# KEY.net
KiCad netlist of a schematic drawn in Altium Designer
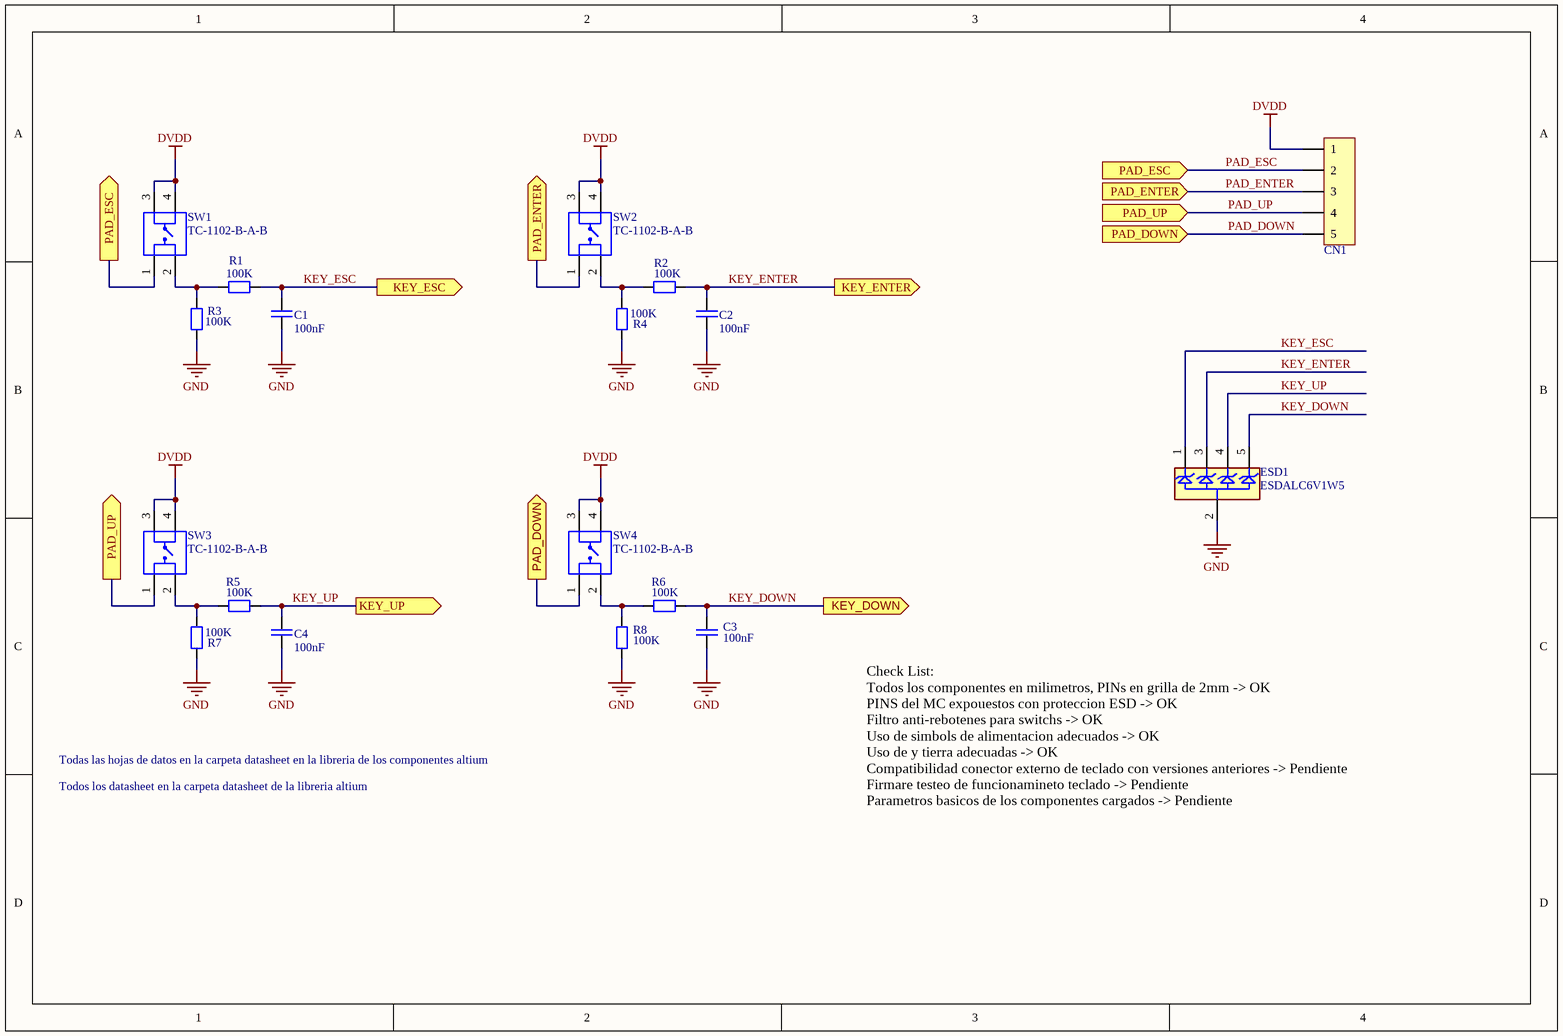
[diagram p0: KEY.SchDoc]

(export (version "E")
  (design (tool "Eeschema 10.0.6"))
  (components
    (comp (ref "C1")
      (value "100nF")
      (footprint "CAP_SM0805_YAGEOCC2_N")
      (description "CAP 100nF SM0805 X7R 25V YAGEO CC2")
      (fields
        (field (name "MANUFACTURER") "Yageo")
        (field (name "MANUFACTURER PART NUMBER") "CC0805KRX7R8BB104")
      )
      (libsource (lib "Yageo") (part "CC0805KRX7R8BB104"))
    )
    (comp (ref "C2")
      (value "100nF")
      (footprint "CAP_SM0805_YAGEOCC2_N")
      (description "CAP 100nF SM0805 X7R 25V YAGEO CC2")
      (fields
        (field (name "MANUFACTURER") "Yageo")
        (field (name "MANUFACTURER PART NUMBER") "CC0805KRX7R8BB104")
      )
      (libsource (lib "Yageo") (part "CC0805KRX7R8BB104"))
    )
    (comp (ref "C3")
      (value "100nF")
      (footprint "CAP_SM0805_YAGEOCC2_N")
      (description "CAP 100nF SM0805 X7R 25V YAGEO CC2")
      (fields
        (field (name "MANUFACTURER") "Yageo")
        (field (name "MANUFACTURER PART NUMBER") "CC0805KRX7R8BB104")
      )
      (libsource (lib "Yageo") (part "CC0805KRX7R8BB104"))
    )
    (comp (ref "C4")
      (value "100nF")
      (footprint "CAP_SM0805_YAGEOCC2_N")
      (description "CAP 100nF SM0805 X7R 25V YAGEO CC2")
      (fields
        (field (name "MANUFACTURER") "Yageo")
        (field (name "MANUFACTURER PART NUMBER") "CC0805KRX7R8BB104")
      )
      (libsource (lib "Yageo") (part "CC0805KRX7R8BB104"))
    )
    (comp (ref "CN1")
      (value "54101-T0605LF")
      (footprint "HEADER PIN 1X5")
      (description "1 x 5 - true hole  2.54mm - Pb free")
      (fields (field (name "MANUFACTURER") "Amphenol ICC"))
      (libsource (lib "header_pin") (part "54101-T0605LF"))
    )
    (comp (ref "ESD1")
      (value "ESDALC6V1W5")
      (footprint "ESDALC6V1W5")
      (fields (field (name "MANUFACTURER") "ST"))
      (libsource (lib "diode") (part "ESDALC6V1W5"))
    )
    (comp (ref "R1")
      (value "100K")
      (footprint "RES_SM0805_YAGEORC_N")
      (description "RES 100K SM0805 YAGEO RC_L")
      (fields
        (field (name "MANUFACTURER") "Yageo")
        (field (name "MANUFACTURER PART NUMBER") "RC0805FR-07100KL")
      )
      (libsource (lib "") (part "RC0805FR-07100KL_1"))
    )
    (comp (ref "R2")
      (value "100K")
      (footprint "RES_SM0805_YAGEORC_N")
      (description "RES 100K SM0805 YAGEO RC_L")
      (fields
        (field (name "MANUFACTURER") "Yageo")
        (field (name "MANUFACTURER PART NUMBER") "RC0805FR-07100KL")
      )
      (libsource (lib "") (part "RC0805FR-07100KL_1"))
    )
    (comp (ref "R3")
      (value "100K")
      (footprint "RES_SM0805_YAGEORC_N")
      (description "RES 100K SM0805 YAGEO RC_L")
      (fields
        (field (name "MANUFACTURER") "Yageo")
        (field (name "MANUFACTURER PART NUMBER") "RC0805FR-07100KL")
      )
      (libsource (lib "Yageo") (part "RC0805FR-07100KL"))
    )
    (comp (ref "R4")
      (value "100K")
      (footprint "RES_SM0805_YAGEORC_N")
      (description "RES 100K SM0805 YAGEO RC_L")
      (fields
        (field (name "MANUFACTURER") "Yageo")
        (field (name "MANUFACTURER PART NUMBER") "RC0805FR-07100KL")
      )
      (libsource (lib "Yageo") (part "RC0805FR-07100KL"))
    )
    (comp (ref "R5")
      (value "100K")
      (footprint "RES_SM0805_YAGEORC_N")
      (description "RES 100K SM0805 YAGEO RC_L")
      (fields
        (field (name "MANUFACTURER") "Yageo")
        (field (name "MANUFACTURER PART NUMBER") "RC0805FR-07100KL")
      )
      (libsource (lib "") (part "RC0805FR-07100KL_1"))
    )
    (comp (ref "R6")
      (value "100K")
      (footprint "RES_SM0805_YAGEORC_N")
      (description "RES 100K SM0805 YAGEO RC_L")
      (fields
        (field (name "MANUFACTURER") "Yageo")
        (field (name "MANUFACTURER PART NUMBER") "RC0805FR-07100KL")
      )
      (libsource (lib "") (part "RC0805FR-07100KL_1"))
    )
    (comp (ref "R7")
      (value "100K")
      (footprint "RES_SM0805_YAGEORC_N")
      (description "RES 100K SM0805 YAGEO RC_L")
      (fields
        (field (name "MANUFACTURER") "Yageo")
        (field (name "MANUFACTURER PART NUMBER") "RC0805FR-07100KL")
      )
      (libsource (lib "Yageo") (part "RC0805FR-07100KL"))
    )
    (comp (ref "R8")
      (value "100K")
      (footprint "RES_SM0805_YAGEORC_N")
      (description "RES 100K SM0805 YAGEO RC_L")
      (fields
        (field (name "MANUFACTURER") "Yageo")
        (field (name "MANUFACTURER PART NUMBER") "RC0805FR-07100KL")
      )
      (libsource (lib "Yageo") (part "RC0805FR-07100KL"))
    )
    (comp (ref "SW1")
      (value "TC-1102-B-A-B")
      (footprint "TC-1102-B-A-B")
      (description "Switch tactile 6x6mm true hole.")
      (fields (field (name "MANUFACTURER") "XKB Connectivity"))
      (libsource (lib "Switches") (part "TC-1102-B-A-B"))
    )
    (comp (ref "SW2")
      (value "TC-1102-B-A-B")
      (footprint "TC-1102-B-A-B")
      (description "Switch tactile 6x6mm true hole.")
      (fields (field (name "MANUFACTURER") "XKB Connectivity"))
      (libsource (lib "Switches") (part "TC-1102-B-A-B"))
    )
    (comp (ref "SW3")
      (value "TC-1102-B-A-B")
      (footprint "TC-1102-B-A-B")
      (description "Switch tactile 6x6mm true hole.")
      (fields (field (name "MANUFACTURER") "XKB Connectivity"))
      (libsource (lib "Switches") (part "TC-1102-B-A-B"))
    )
    (comp (ref "SW4")
      (value "TC-1102-B-A-B")
      (footprint "TC-1102-B-A-B")
      (description "Switch tactile 6x6mm true hole.")
      (fields (field (name "MANUFACTURER") "XKB Connectivity"))
      (libsource (lib "Switches") (part "TC-1102-B-A-B"))
    )
  )
  (nets
    (net (code "1") (name "/KEY_DOWN") (class "Default")
      (node (ref "C3") (pin "1") (pintype "passive"))
      (node (ref "ESD1") (pin "5") (pinfunction "I/04_5") (pintype "passive"))
      (node (ref "R6") (pin "2") (pintype "passive"))
    )
    (net (code "2") (name "/KEY_ENTER") (class "Default")
      (node (ref "C2") (pin "1") (pintype "passive"))
      (node (ref "ESD1") (pin "3") (pinfunction "I/02_3") (pintype "passive"))
      (node (ref "R2") (pin "2") (pintype "passive"))
    )
    (net (code "3") (name "/KEY_ESC") (class "Default")
      (node (ref "C1") (pin "1") (pintype "passive"))
      (node (ref "ESD1") (pin "1") (pinfunction "I/01_1") (pintype "passive"))
      (node (ref "R1") (pin "2") (pintype "passive"))
    )
    (net (code "4") (name "/KEY_UP") (class "Default")
      (node (ref "C4") (pin "1") (pintype "passive"))
      (node (ref "ESD1") (pin "4") (pinfunction "I/03_4") (pintype "passive"))
      (node (ref "R5") (pin "2") (pintype "passive"))
    )
    (net (code "5") (name "/PAD_DOWN") (class "Default")
      (node (ref "CN1") (pin "5") (pinfunction "5_5") (pintype "passive"))
      (node (ref "SW4") (pin "1") (pinfunction "1_1") (pintype "passive"))
    )
    (net (code "6") (name "/PAD_ENTER") (class "Default")
      (node (ref "CN1") (pin "3") (pinfunction "3_3") (pintype "passive"))
      (node (ref "SW2") (pin "1") (pinfunction "1_1") (pintype "passive"))
    )
    (net (code "7") (name "/PAD_ESC") (class "Default")
      (node (ref "CN1") (pin "2") (pinfunction "2_2") (pintype "passive"))
      (node (ref "SW1") (pin "1") (pinfunction "1_1") (pintype "passive"))
    )
    (net (code "8") (name "/PAD_UP") (class "Default")
      (node (ref "CN1") (pin "4") (pinfunction "4_4") (pintype "passive"))
      (node (ref "SW3") (pin "1") (pinfunction "1_1") (pintype "passive"))
    )
    (net (code "9") (name "DVDD") (class "Default")
      (node (ref "CN1") (pin "1") (pinfunction "1_1") (pintype "passive"))
      (node (ref "SW1") (pin "3") (pinfunction "g_3") (pintype "passive"))
      (node (ref "SW1") (pin "4") (pinfunction "4_4") (pintype "passive"))
      (node (ref "SW2") (pin "3") (pinfunction "g_3") (pintype "passive"))
      (node (ref "SW2") (pin "4") (pinfunction "4_4") (pintype "passive"))
      (node (ref "SW3") (pin "3") (pinfunction "g_3") (pintype "passive"))
      (node (ref "SW3") (pin "4") (pinfunction "4_4") (pintype "passive"))
      (node (ref "SW4") (pin "3") (pinfunction "g_3") (pintype "passive"))
      (node (ref "SW4") (pin "4") (pinfunction "4_4") (pintype "passive"))
    )
    (net (code "10") (name "GND") (class "Default")
      (node (ref "C1") (pin "2") (pintype "passive"))
      (node (ref "C2") (pin "2") (pintype "passive"))
      (node (ref "C3") (pin "2") (pintype "passive"))
      (node (ref "C4") (pin "2") (pintype "passive"))
      (node (ref "ESD1") (pin "2") (pinfunction "GND_2") (pintype "passive"))
      (node (ref "R3") (pin "1") (pintype "passive"))
      (node (ref "R4") (pin "1") (pintype "passive"))
      (node (ref "R7") (pin "1") (pintype "passive"))
      (node (ref "R8") (pin "1") (pintype "passive"))
    )
    (net (code "11") (name "Net-(R1-Pad1)") (class "Default")
      (node (ref "R1") (pin "1") (pintype "passive"))
      (node (ref "R3") (pin "2") (pintype "passive"))
      (node (ref "SW1") (pin "2") (pinfunction "2_2") (pintype "passive"))
    )
    (net (code "12") (name "Net-(R2-Pad1)") (class "Default")
      (node (ref "R2") (pin "1") (pintype "passive"))
      (node (ref "R4") (pin "2") (pintype "passive"))
      (node (ref "SW2") (pin "2") (pinfunction "2_2") (pintype "passive"))
    )
    (net (code "13") (name "Net-(R5-Pad1)") (class "Default")
      (node (ref "R5") (pin "1") (pintype "passive"))
      (node (ref "R7") (pin "2") (pintype "passive"))
      (node (ref "SW3") (pin "2") (pinfunction "2_2") (pintype "passive"))
    )
    (net (code "14") (name "Net-(R6-Pad1)") (class "Default")
      (node (ref "R6") (pin "1") (pintype "passive"))
      (node (ref "R8") (pin "2") (pintype "passive"))
      (node (ref "SW4") (pin "2") (pinfunction "2_2") (pintype "passive"))
    )
  )
)
